# filter_block.net
KiCad netlist of a schematic drawn in Altium Designer
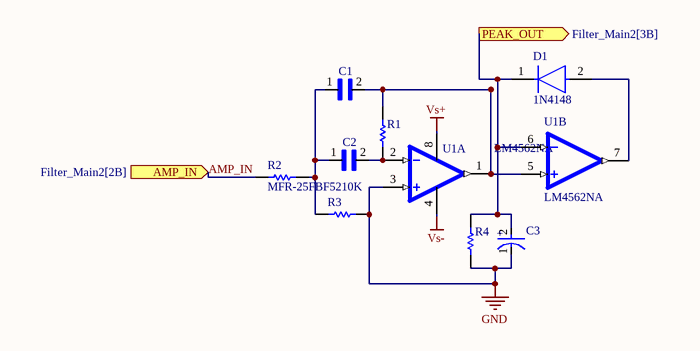
[diagram p0: filter_block.SchDoc]

(export (version "E")
  (design (tool "Eeschema 10.0.6"))
  (components
    (comp (ref "C1")
      (value "ECWFD2W105Q1")
      (footprint "PcbLib1:CAPRR1000W60L1260T920H1390")
      (description "Capacitor film")
      (libsource (lib "Schlib1") (part "ECWFD2W105Q1"))
    )
    (comp (ref "C2")
      (value "ECWFD2W105Q1")
      (footprint "PcbLib1:CAPRR1000W60L1260T920H1390")
      (description "Capacitor film")
      (libsource (lib "Schlib1") (part "ECWFD2W105Q1"))
    )
    (comp (ref "C3")
      (value "CAPPRD250W50D630H1250")
      (footprint "CAPPRD250W50D630H1250")
      (description "Capacitor Electrolyte")
      (libsource (lib "Schlib1") (part "CAPPRD250W50D630H1250"))
    )
    (comp (ref "D1")
      (value "1N4148")
      (footprint "FP-017AG-MFG")
      (description "DIODE GEN PURP 100V 200MA DO35")
      (fields (field (name "VOLTAGE") "100V"))
      (libsource (lib "Altium Content Vault") (part "d7152d700b627762746794eb795d46e"))
    )
    (comp (ref "R1")
      (value "MFR-25FBF5210K")
      (footprint "RESA60-630X240")
      (description "Axial Resistor, 10 KOhm, +/- 1%, 0.25 W, -55 to 155 degC, 2-Pin THD, RoHS, Bulk")
      (fields (field (name "TOLERANCE") "1%") (field (name "MANUFACTURER") "Yageo"))
      (libsource (lib "Altium Content Vault") (part "RES-2"))
    )
    (comp (ref "R2")
      (value "MFR-25FBF5210K")
      (footprint "RESA60-630X240")
      (description "Axial Resistor, 10 KOhm, +/- 1%, 0.25 W, -55 to 155 degC, 2-Pin THD, RoHS, Bulk")
      (fields (field (name "TOLERANCE") "1%") (field (name "MANUFACTURER") "Yageo"))
      (libsource (lib "Altium Content Vault") (part "RES-2"))
    )
    (comp (ref "R3")
      (value "MFR-25FBF5210K")
      (footprint "RESA60-630X240")
      (description "Axial Resistor, 10 KOhm, +/- 1%, 0.25 W, -55 to 155 degC, 2-Pin THD, RoHS, Bulk")
      (fields (field (name "TOLERANCE") "1%") (field (name "MANUFACTURER") "Yageo"))
      (libsource (lib "Altium Content Vault") (part "RES-2"))
    )
    (comp (ref "R4")
      (value "MFR-25FBF5210K")
      (footprint "RESA60-630X240")
      (description "Axial Resistor, 10 KOhm, +/- 1%, 0.25 W, -55 to 155 degC, 2-Pin THD, RoHS, Bulk")
      (fields (field (name "TOLERANCE") "1%") (field (name "MANUFACTURER") "Yageo"))
      (libsource (lib "Altium Content Vault") (part "RES-2"))
    )
    (comp (ref "U1")
      (value "LM4562NA")
      (footprint "DIP794W45P254L959H508Q8")
      (description "LM4562 2 - Dual Channels per IC Audio Amplifier Evaluation Board")
      (fields (field (name "MF") "Texas Instruments"))
      (libsource (lib "Schlib1") (part "LM4562NA"))
    )
  )
  (nets
    (net (code "1") (name "/AMP_IN") (class "Default")
      (node (ref "R2") (pin "1") (pinfunction "1_1") (pintype "passive"))
    )
    (net (code "2") (name "/PEAK_OUT") (class "Default")
      (node (ref "C3") (pin "2") (pinfunction "A_2") (pintype "passive"))
      (node (ref "D1") (pin "1") (pinfunction "C_1") (pintype "passive"))
      (node (ref "R4") (pin "2") (pinfunction "2_2") (pintype "passive"))
      (node (ref "U1") (pin "6") (pinfunction "INB-_6") (pintype "input"))
    )
    (net (code "3") (name "GND") (class "Default")
      (node (ref "C3") (pin "1") (pinfunction "C_1") (pintype "passive"))
      (node (ref "R3") (pin "2") (pinfunction "2_2") (pintype "passive"))
      (node (ref "R4") (pin "1") (pinfunction "1_1") (pintype "passive"))
      (node (ref "U1") (pin "3") (pinfunction "INA+_3") (pintype "input"))
    )
    (net (code "4") (name "Net-(C1-Pad1)") (class "Default")
      (node (ref "C1") (pin "1") (pinfunction "1_1") (pintype "passive"))
      (node (ref "C2") (pin "1") (pinfunction "1_1") (pintype "passive"))
      (node (ref "R2") (pin "2") (pinfunction "2_2") (pintype "passive"))
      (node (ref "R3") (pin "1") (pinfunction "1_1") (pintype "passive"))
    )
    (net (code "5") (name "Net-(D1-A)") (class "Default")
      (node (ref "D1") (pin "2") (pinfunction "A_2") (pintype "passive"))
      (node (ref "U1") (pin "7") (pinfunction "OUTB_7") (pintype "output"))
    )
    (net (code "6") (name "Net-(U1A-INA-)") (class "Default")
      (node (ref "C2") (pin "2") (pinfunction "2_2") (pintype "passive"))
      (node (ref "R1") (pin "1") (pinfunction "1_1") (pintype "passive"))
      (node (ref "U1") (pin "2") (pinfunction "INA-_2") (pintype "input"))
    )
    (net (code "7") (name "Net-(U1A-OUTA)") (class "Default")
      (node (ref "C1") (pin "2") (pinfunction "2_2") (pintype "passive"))
      (node (ref "R1") (pin "2") (pinfunction "2_2") (pintype "passive"))
      (node (ref "U1") (pin "1") (pinfunction "OUTA_1") (pintype "output"))
      (node (ref "U1") (pin "5") (pinfunction "INB+_5") (pintype "input"))
    )
    (net (code "8") (name "Vs+") (class "Default")
      (node (ref "U1") (pin "8") (pinfunction "V+_8") (pintype "power_in"))
    )
    (net (code "9") (name "Vs-") (class "Default")
      (node (ref "U1") (pin "4") (pinfunction "V-_4") (pintype "power_in"))
    )
  )
)
